# uc4h_slcan_adapter_v101.net
KiCad netlist of a schematic drawn in EAGLE
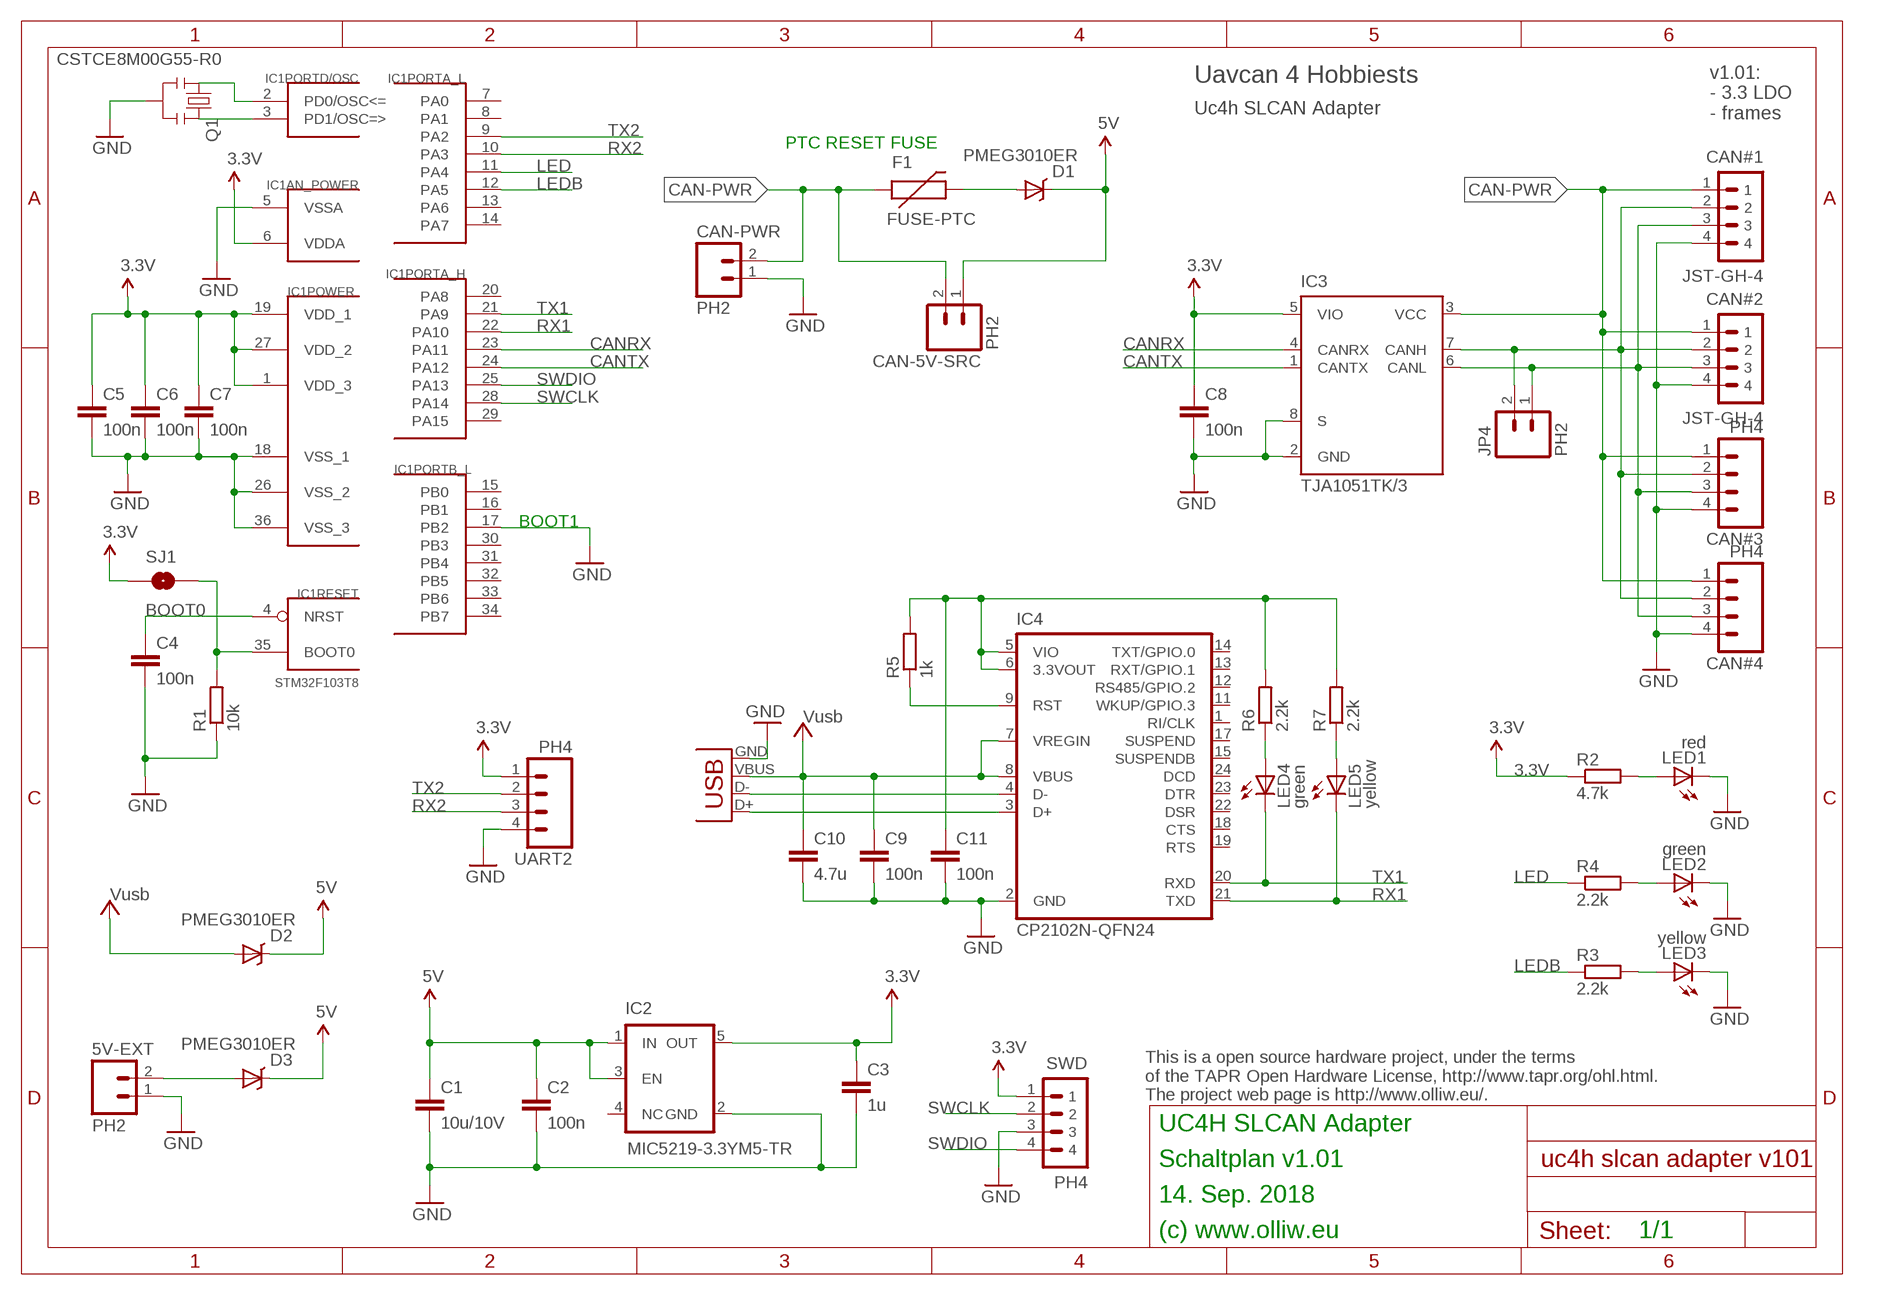
[diagram p0: schematic, sheet 1]

(export (version "E")
  (design (tool "Eeschema 10.0.6"))
  (components
    (comp (ref "5V-EXT")
      (value "PH2")
      (footprint "eagle-import:1X02")
      (libsource (lib "eagle-import") (part "M02PTH"))
    )
    (comp (ref "C1")
      (value "10u/10V")
      (footprint "eagle-import:C1206")
      (libsource (lib "eagle-import") (part "C-EUC1206"))
    )
    (comp (ref "C2")
      (value "100n")
      (footprint "eagle-import:C0603K")
      (libsource (lib "eagle-import") (part "C-EUC0603K"))
    )
    (comp (ref "C3")
      (value "1u")
      (footprint "eagle-import:C0603K")
      (libsource (lib "eagle-import") (part "C-EUC0603K"))
    )
    (comp (ref "C4")
      (value "100n")
      (footprint "eagle-import:C0603K")
      (libsource (lib "eagle-import") (part "C-EUC0603K"))
    )
    (comp (ref "C5")
      (value "100n")
      (footprint "eagle-import:C0603K")
      (libsource (lib "eagle-import") (part "C-EUC0603K"))
    )
    (comp (ref "C6")
      (value "100n")
      (footprint "eagle-import:C0603K")
      (libsource (lib "eagle-import") (part "C-EUC0603K"))
    )
    (comp (ref "C7")
      (value "100n")
      (footprint "eagle-import:C0603K")
      (libsource (lib "eagle-import") (part "C-EUC0603K"))
    )
    (comp (ref "C8")
      (value "100n")
      (footprint "eagle-import:C0603K")
      (libsource (lib "eagle-import") (part "C-EUC0603K"))
    )
    (comp (ref "C9")
      (value "100n")
      (footprint "eagle-import:C0603K")
      (libsource (lib "eagle-import") (part "C-EUC0603K"))
    )
    (comp (ref "C10")
      (value "4.7u")
      (footprint "eagle-import:C0805")
      (libsource (lib "eagle-import") (part "C-EUC0805"))
    )
    (comp (ref "C11")
      (value "100n")
      (footprint "eagle-import:C0603K")
      (libsource (lib "eagle-import") (part "C-EUC0603K"))
    )
    (comp (ref "CAN#1")
      (value "JST-GH-4")
      (footprint "eagle-import:SM04B-GHS-TB")
      (libsource (lib "eagle-import") (part "JST-GH-4"))
    )
    (comp (ref "CAN#2")
      (value "JST-GH-4")
      (footprint "eagle-import:SM04B-GHS-TB")
      (libsource (lib "eagle-import") (part "JST-GH-4"))
    )
    (comp (ref "CAN#3")
      (value "PH4")
      (footprint "eagle-import:1X04")
      (libsource (lib "eagle-import") (part "M04PTH"))
    )
    (comp (ref "CAN#4")
      (value "PH4")
      (footprint "eagle-import:1X04")
      (libsource (lib "eagle-import") (part "M04PTH"))
    )
    (comp (ref "CAN-5V-SRC")
      (value "PH2")
      (footprint "eagle-import:1X02")
      (libsource (lib "eagle-import") (part "M02PTH"))
    )
    (comp (ref "CAN-PWR")
      (value "PH2")
      (footprint "eagle-import:1X02")
      (libsource (lib "eagle-import") (part "M02PTH"))
    )
    (comp (ref "D1")
      (value "PMEG3010ER")
      (footprint "eagle-import:SOD123W-DIODE")
      (libsource (lib "eagle-import") (part "DIODE-SCHOTTKYSOD123-W"))
    )
    (comp (ref "D2")
      (value "PMEG3010ER")
      (footprint "eagle-import:SOD123W-DIODE")
      (libsource (lib "eagle-import") (part "DIODE-SCHOTTKYSOD123-W"))
    )
    (comp (ref "D3")
      (value "PMEG3010ER")
      (footprint "eagle-import:SOD123W-DIODE")
      (libsource (lib "eagle-import") (part "DIODE-SCHOTTKYSOD123-W"))
    )
    (comp (ref "F1")
      (value "FUSE-PTC")
      (footprint "eagle-import:FUSE-1206")
      (libsource (lib "eagle-import") (part "FUSE-PTC"))
    )
    (comp (ref "IC1")
      (value "STM32F103T8")
      (footprint "eagle-import:VFQFPN36")
      (libsource (lib "eagle-import") (part "STM32F10XTXU6"))
    )
    (comp (ref "IC2")
      (value "MIC5219-3.3YM5-TR")
      (footprint "eagle-import:SOT23-5")
      (libsource (lib "eagle-import") (part "V_REG_TPS76433SOT23-5"))
    )
    (comp (ref "IC3")
      (value "TJA1051TK/3")
      (footprint "eagle-import:HVSON8")
      (libsource (lib "eagle-import") (part "TJA1051TK/3"))
    )
    (comp (ref "IC4")
      (value "CP2102N-QFN24")
      (footprint "eagle-import:QFN24-CP2102N")
      (libsource (lib "eagle-import") (part "CP2102N-QFN24"))
    )
    (comp (ref "JP4")
      (value "PH2")
      (footprint "eagle-import:1X02")
      (libsource (lib "eagle-import") (part "M02PTH"))
    )
    (comp (ref "LED1")
      (value "red")
      (footprint "eagle-import:CHIPLED_0603")
      (libsource (lib "eagle-import") (part "LEDCHIPLED_0603"))
    )
    (comp (ref "LED2")
      (value "green")
      (footprint "eagle-import:CHIPLED_0603")
      (libsource (lib "eagle-import") (part "LEDCHIPLED_0603"))
    )
    (comp (ref "LED3")
      (value "yellow")
      (footprint "eagle-import:CHIPLED_0603")
      (libsource (lib "eagle-import") (part "LEDCHIPLED_0603"))
    )
    (comp (ref "LED4")
      (value "green")
      (footprint "eagle-import:CHIPLED_0603")
      (libsource (lib "eagle-import") (part "LEDCHIPLED_0603"))
    )
    (comp (ref "LED5")
      (value "yellow")
      (footprint "eagle-import:CHIPLED_0603")
      (libsource (lib "eagle-import") (part "LEDCHIPLED_0603"))
    )
    (comp (ref "Q1")
      (value "CSTCE8M00G55-R0")
      (footprint "eagle-import:RESONATOR-SMD")
      (libsource (lib "eagle-import") (part "RESONATORSMD"))
    )
    (comp (ref "R1")
      (value "10k")
      (footprint "eagle-import:R0603")
      (libsource (lib "eagle-import") (part "R-EU_R0603"))
    )
    (comp (ref "R2")
      (value "4.7k")
      (footprint "eagle-import:R0603")
      (libsource (lib "eagle-import") (part "R-EU_R0603"))
    )
    (comp (ref "R3")
      (value "2.2k")
      (footprint "eagle-import:R0603")
      (libsource (lib "eagle-import") (part "R-EU_R0603"))
    )
    (comp (ref "R4")
      (value "2.2k")
      (footprint "eagle-import:R0603")
      (libsource (lib "eagle-import") (part "R-EU_R0603"))
    )
    (comp (ref "R5")
      (value "1k")
      (footprint "eagle-import:R0603")
      (libsource (lib "eagle-import") (part "R-EU_R0603"))
    )
    (comp (ref "R6")
      (value "2.2k")
      (footprint "eagle-import:R0603")
      (libsource (lib "eagle-import") (part "R-EU_R0603"))
    )
    (comp (ref "R7")
      (value "2.2k")
      (footprint "eagle-import:R0603")
      (libsource (lib "eagle-import") (part "R-EU_R0603"))
    )
    (comp (ref "SJ1")
      (value "BOOT0")
      (footprint "eagle-import:SJ_2S-NO")
      (libsource (lib "eagle-import") (part "SOLDERJUMPERNO"))
    )
    (comp (ref "SWD")
      (value "PH4")
      (footprint "eagle-import:4X1_1P27_OCT_BILEX")
      (libsource (lib "eagle-import") (part "P4X1_1P27-OCT_BILEX"))
    )
    (comp (ref "UART2")
      (value "PH4")
      (footprint "eagle-import:1X04")
      (libsource (lib "eagle-import") (part "M04PTH"))
    )
    (comp (ref "USB")
      (value "Amphenol 10118192-0001LF")
      (footprint "eagle-import:USB-MICROB")
      (libsource (lib "eagle-import") (part "USB-MICROB"))
    )
  )
  (nets
    (net (code "1") (name "/CANRX") (class "Default")
      (node (ref "IC1") (pin "23") (pinfunction "PA11_23") (pintype "bidirectional"))
      (node (ref "IC3") (pin "4") (pinfunction "CANRX_4") (pintype "output"))
    )
    (net (code "2") (name "/CANTX") (class "Default")
      (node (ref "IC1") (pin "24") (pinfunction "PA12_24") (pintype "bidirectional"))
      (node (ref "IC3") (pin "1") (pinfunction "CANTX_1") (pintype "input"))
    )
    (net (code "3") (name "/LED") (class "Default")
      (node (ref "IC1") (pin "11") (pinfunction "PA4_11") (pintype "bidirectional"))
      (node (ref "R4") (pin "1") (pinfunction "1_1") (pintype "passive"))
    )
    (net (code "4") (name "/LEDB") (class "Default")
      (node (ref "IC1") (pin "12") (pinfunction "PA5_12") (pintype "bidirectional"))
      (node (ref "R3") (pin "1") (pinfunction "1_1") (pintype "passive"))
    )
    (net (code "5") (name "/RX1") (class "Default")
      (node (ref "IC1") (pin "22") (pinfunction "PA10_22") (pintype "bidirectional"))
      (node (ref "IC4") (pin "21") (pinfunction "TXD_21") (pintype "output"))
      (node (ref "LED5") (pin "C") (pinfunction "C_C") (pintype "passive"))
    )
    (net (code "6") (name "/RX2") (class "Default")
      (node (ref "IC1") (pin "10") (pinfunction "PA3_10") (pintype "bidirectional"))
      (node (ref "UART2") (pin "3") (pinfunction "3_3") (pintype "passive"))
    )
    (net (code "7") (name "/SWCLK") (class "Default")
      (node (ref "IC1") (pin "28") (pinfunction "PA14_28") (pintype "bidirectional"))
      (node (ref "SWD") (pin "2") (pinfunction "2_2") (pintype "passive"))
    )
    (net (code "8") (name "/SWDIO") (class "Default")
      (node (ref "IC1") (pin "25") (pinfunction "PA13_25") (pintype "bidirectional"))
      (node (ref "SWD") (pin "4") (pinfunction "4_4") (pintype "passive"))
    )
    (net (code "9") (name "/TX1") (class "Default")
      (node (ref "IC1") (pin "21") (pinfunction "PA9_21") (pintype "bidirectional"))
      (node (ref "IC4") (pin "20") (pinfunction "RXD_20") (pintype "input"))
      (node (ref "LED4") (pin "C") (pinfunction "C_C") (pintype "passive"))
    )
    (net (code "10") (name "/TX2") (class "Default")
      (node (ref "IC1") (pin "9") (pinfunction "PA2_9") (pintype "bidirectional"))
      (node (ref "UART2") (pin "2") (pinfunction "2_2") (pintype "passive"))
    )
    (net (code "11") (name "3.3V") (class "Default")
      (node (ref "C3") (pin "1") (pinfunction "1_1") (pintype "passive"))
      (node (ref "C5") (pin "1") (pinfunction "1_1") (pintype "passive"))
      (node (ref "C6") (pin "1") (pinfunction "1_1") (pintype "passive"))
      (node (ref "C7") (pin "1") (pinfunction "1_1") (pintype "passive"))
      (node (ref "C8") (pin "1") (pinfunction "1_1") (pintype "passive"))
      (node (ref "IC1") (pin "1") (pinfunction "VDD_3_1") (pintype "power_in"))
      (node (ref "IC1") (pin "19") (pinfunction "VDD_1_19") (pintype "power_in"))
      (node (ref "IC1") (pin "27") (pinfunction "VDD_2_27") (pintype "power_in"))
      (node (ref "IC1") (pin "6") (pinfunction "VDDA_6") (pintype "power_in"))
      (node (ref "IC2") (pin "5") (pinfunction "OUT_5") (pintype "output"))
      (node (ref "IC3") (pin "5") (pinfunction "VIO_5") (pintype "power_in"))
      (node (ref "R2") (pin "1") (pinfunction "1_1") (pintype "passive"))
      (node (ref "SJ1") (pin "1") (pinfunction "1_1") (pintype "passive"))
      (node (ref "SWD") (pin "1") (pinfunction "1_1") (pintype "passive"))
      (node (ref "UART2") (pin "1") (pinfunction "1_1") (pintype "passive"))
    )
    (net (code "12") (name "5V") (class "Default")
      (node (ref "C1") (pin "1") (pinfunction "1_1") (pintype "passive"))
      (node (ref "C2") (pin "1") (pinfunction "1_1") (pintype "passive"))
      (node (ref "CAN-5V-SRC") (pin "1") (pinfunction "1_1") (pintype "passive"))
      (node (ref "D1") (pin "C") (pinfunction "C_C") (pintype "passive"))
      (node (ref "D2") (pin "C") (pinfunction "C_C") (pintype "passive"))
      (node (ref "D3") (pin "C") (pinfunction "C_C") (pintype "passive"))
      (node (ref "IC2") (pin "1") (pinfunction "IN_1") (pintype "power_in"))
      (node (ref "IC2") (pin "3") (pinfunction "EN_3") (pintype "input"))
    )
    (net (code "13") (name "CAN-PWR") (class "Default")
      (node (ref "CAN#1") (pin "1") (pinfunction "1_1") (pintype "passive"))
      (node (ref "CAN#2") (pin "1") (pinfunction "1_1") (pintype "passive"))
      (node (ref "CAN#3") (pin "1") (pinfunction "1_1") (pintype "passive"))
      (node (ref "CAN#4") (pin "1") (pinfunction "1_1") (pintype "passive"))
      (node (ref "CAN-5V-SRC") (pin "2") (pinfunction "2_2") (pintype "passive"))
      (node (ref "CAN-PWR") (pin "2") (pinfunction "2_2") (pintype "passive"))
      (node (ref "F1") (pin "3") (pinfunction "1_3") (pintype "bidirectional"))
      (node (ref "IC3") (pin "3") (pinfunction "VCC_3") (pintype "power_in"))
    )
    (net (code "14") (name "GND") (class "Default")
      (node (ref "5V-EXT") (pin "1") (pinfunction "1_1") (pintype "passive"))
      (node (ref "C1") (pin "2") (pinfunction "2_2") (pintype "passive"))
      (node (ref "C10") (pin "2") (pinfunction "2_2") (pintype "passive"))
      (node (ref "C11") (pin "2") (pinfunction "2_2") (pintype "passive"))
      (node (ref "C2") (pin "2") (pinfunction "2_2") (pintype "passive"))
      (node (ref "C3") (pin "2") (pinfunction "2_2") (pintype "passive"))
      (node (ref "C4") (pin "2") (pinfunction "2_2") (pintype "passive"))
      (node (ref "C5") (pin "2") (pinfunction "2_2") (pintype "passive"))
      (node (ref "C6") (pin "2") (pinfunction "2_2") (pintype "passive"))
      (node (ref "C7") (pin "2") (pinfunction "2_2") (pintype "passive"))
      (node (ref "C8") (pin "2") (pinfunction "2_2") (pintype "passive"))
      (node (ref "C9") (pin "2") (pinfunction "2_2") (pintype "passive"))
      (node (ref "CAN#1") (pin "4") (pinfunction "4_4") (pintype "passive"))
      (node (ref "CAN#2") (pin "4") (pinfunction "4_4") (pintype "passive"))
      (node (ref "CAN#3") (pin "4") (pinfunction "4_4") (pintype "passive"))
      (node (ref "CAN#4") (pin "4") (pinfunction "4_4") (pintype "passive"))
      (node (ref "CAN-PWR") (pin "1") (pinfunction "1_1") (pintype "passive"))
      (node (ref "IC1") (pin "17") (pinfunction "PB2_17") (pintype "bidirectional"))
      (node (ref "IC1") (pin "18") (pinfunction "VSS_1_18") (pintype "power_in"))
      (node (ref "IC1") (pin "26") (pinfunction "VSS_2_26") (pintype "power_in"))
      (node (ref "IC1") (pin "36") (pinfunction "VSS_3_36") (pintype "power_in"))
      (node (ref "IC1") (pin "5") (pinfunction "VSSA_5") (pintype "power_in"))
      (node (ref "IC2") (pin "2") (pinfunction "GND_2") (pintype "power_in"))
      (node (ref "IC3") (pin "2") (pinfunction "GND_2") (pintype "power_in"))
      (node (ref "IC3") (pin "8") (pinfunction "S_8") (pintype "input"))
      (node (ref "IC4") (pin "2") (pinfunction "GND_2") (pintype "power_in"))
      (node (ref "LED1") (pin "C") (pinfunction "C_C") (pintype "passive"))
      (node (ref "LED2") (pin "C") (pinfunction "C_C") (pintype "passive"))
      (node (ref "LED3") (pin "C") (pinfunction "C_C") (pintype "passive"))
      (node (ref "Q1") (pin "2") (pinfunction "2_2") (pintype "passive"))
      (node (ref "R1") (pin "1") (pinfunction "1_1") (pintype "passive"))
      (node (ref "SWD") (pin "3") (pinfunction "3_3") (pintype "passive"))
      (node (ref "UART2") (pin "4") (pinfunction "4_4") (pintype "passive"))
      (node (ref "USB") (pin "GND") (pinfunction "GND_GND") (pintype "bidirectional"))
    )
    (net (code "15") (name "Net-(5V-EXT-Pad2)") (class "Default")
      (node (ref "5V-EXT") (pin "2") (pinfunction "2_2") (pintype "passive"))
      (node (ref "D3") (pin "A") (pinfunction "A_A") (pintype "passive"))
    )
    (net (code "16") (name "Net-(F1-2)") (class "Default")
      (node (ref "D1") (pin "A") (pinfunction "A_A") (pintype "passive"))
      (node (ref "F1") (pin "4") (pinfunction "2_4") (pintype "bidirectional"))
    )
    (net (code "17") (name "Net-(IC1E-PD0{slash}OSC<=)") (class "Default")
      (node (ref "IC1") (pin "2") (pinfunction "PD0/OSC<=_2") (pintype "bidirectional"))
      (node (ref "Q1") (pin "1") (pinfunction "1_1") (pintype "passive"))
    )
    (net (code "18") (name "Net-(IC1E-PD1{slash}OSC=>)") (class "Default")
      (node (ref "IC1") (pin "3") (pinfunction "PD1/OSC=>_3") (pintype "bidirectional"))
      (node (ref "Q1") (pin "3") (pinfunction "3_3") (pintype "passive"))
    )
    (net (code "19") (name "Net-(IC1G-BOOT0)") (class "Default")
      (node (ref "IC1") (pin "35") (pinfunction "BOOT0_35") (pintype "input"))
      (node (ref "R1") (pin "2") (pinfunction "2_2") (pintype "passive"))
      (node (ref "SJ1") (pin "2") (pinfunction "2_2") (pintype "passive"))
    )
    (net (code "20") (name "Net-(IC1G-NRST)") (class "Default")
      (node (ref "C4") (pin "1") (pinfunction "1_1") (pintype "passive"))
      (node (ref "IC1") (pin "4") (pinfunction "NRST_4") (pintype "input"))
    )
    (net (code "21") (name "Net-(IC3-CANH)") (class "Default")
      (node (ref "CAN#1") (pin "2") (pinfunction "2_2") (pintype "passive"))
      (node (ref "CAN#2") (pin "2") (pinfunction "2_2") (pintype "passive"))
      (node (ref "CAN#3") (pin "2") (pinfunction "2_2") (pintype "passive"))
      (node (ref "CAN#4") (pin "2") (pinfunction "2_2") (pintype "passive"))
      (node (ref "IC3") (pin "7") (pinfunction "CANH_7") (pintype "bidirectional"))
      (node (ref "JP4") (pin "2") (pinfunction "2_2") (pintype "passive"))
    )
    (net (code "22") (name "Net-(IC3-CANL)") (class "Default")
      (node (ref "CAN#1") (pin "3") (pinfunction "3_3") (pintype "passive"))
      (node (ref "CAN#2") (pin "3") (pinfunction "3_3") (pintype "passive"))
      (node (ref "CAN#3") (pin "3") (pinfunction "3_3") (pintype "passive"))
      (node (ref "CAN#4") (pin "3") (pinfunction "3_3") (pintype "passive"))
      (node (ref "IC3") (pin "6") (pinfunction "CANL_6") (pintype "bidirectional"))
      (node (ref "JP4") (pin "1") (pinfunction "1_1") (pintype "passive"))
    )
    (net (code "23") (name "Net-(IC4-3.3VOUT)") (class "Default")
      (node (ref "C11") (pin "1") (pinfunction "1_1") (pintype "passive"))
      (node (ref "IC4") (pin "5") (pinfunction "VIO_5") (pintype "power_in"))
      (node (ref "IC4") (pin "6") (pinfunction "3.3VOUT_6") (pintype "power_in"))
      (node (ref "R5") (pin "2") (pinfunction "2_2") (pintype "passive"))
      (node (ref "R6") (pin "2") (pinfunction "2_2") (pintype "passive"))
      (node (ref "R7") (pin "2") (pinfunction "2_2") (pintype "passive"))
    )
    (net (code "24") (name "Net-(IC4-D+)") (class "Default")
      (node (ref "IC4") (pin "3") (pinfunction "D+_3") (pintype "bidirectional"))
      (node (ref "USB") (pin "D+") (pinfunction "D+_D+") (pintype "bidirectional"))
    )
    (net (code "25") (name "Net-(IC4-D-)") (class "Default")
      (node (ref "IC4") (pin "4") (pinfunction "D-_4") (pintype "bidirectional"))
      (node (ref "USB") (pin "D-") (pinfunction "D-_D-") (pintype "bidirectional"))
    )
    (net (code "26") (name "Net-(IC4-RST)") (class "Default")
      (node (ref "IC4") (pin "9") (pinfunction "RST_9") (pintype "input"))
      (node (ref "R5") (pin "1") (pinfunction "1_1") (pintype "passive"))
    )
    (net (code "27") (name "Net-(LED1-PadA)") (class "Default")
      (node (ref "LED1") (pin "A") (pinfunction "A_A") (pintype "passive"))
      (node (ref "R2") (pin "2") (pinfunction "2_2") (pintype "passive"))
    )
    (net (code "28") (name "Net-(LED2-PadA)") (class "Default")
      (node (ref "LED2") (pin "A") (pinfunction "A_A") (pintype "passive"))
      (node (ref "R4") (pin "2") (pinfunction "2_2") (pintype "passive"))
    )
    (net (code "29") (name "Net-(LED3-PadA)") (class "Default")
      (node (ref "LED3") (pin "A") (pinfunction "A_A") (pintype "passive"))
      (node (ref "R3") (pin "2") (pinfunction "2_2") (pintype "passive"))
    )
    (net (code "30") (name "Net-(LED4-PadA)") (class "Default")
      (node (ref "LED4") (pin "A") (pinfunction "A_A") (pintype "passive"))
      (node (ref "R6") (pin "1") (pinfunction "1_1") (pintype "passive"))
    )
    (net (code "31") (name "Net-(LED5-PadA)") (class "Default")
      (node (ref "LED5") (pin "A") (pinfunction "A_A") (pintype "passive"))
      (node (ref "R7") (pin "1") (pinfunction "1_1") (pintype "passive"))
    )
    (net (code "32") (name "Vusb") (class "Default")
      (node (ref "C10") (pin "1") (pinfunction "1_1") (pintype "passive"))
      (node (ref "C9") (pin "1") (pinfunction "1_1") (pintype "passive"))
      (node (ref "D2") (pin "A") (pinfunction "A_A") (pintype "passive"))
      (node (ref "IC4") (pin "7") (pinfunction "VREGIN_7") (pintype "power_in"))
      (node (ref "IC4") (pin "8") (pinfunction "VBUS_8") (pintype "input"))
      (node (ref "USB") (pin "VBUS") (pinfunction "VBUS_VBUS") (pintype "bidirectional"))
    )
    (net (code "33") (name "unconnected-(IC1B-PA8-Pad20)") (class "Default")
      (node (ref "IC1") (pin "20") (pinfunction "PA8_20") (pintype "bidirectional"))
    )
    (net (code "34") (name "unconnected-(IC1B-PA15-Pad29)") (class "Default")
      (node (ref "IC1") (pin "29") (pinfunction "PA15_29") (pintype "bidirectional"))
    )
    (net (code "35") (name "unconnected-(IC1C-PA0-Pad7)") (class "Default")
      (node (ref "IC1") (pin "7") (pinfunction "PA0_7") (pintype "bidirectional"))
    )
    (net (code "36") (name "unconnected-(IC1C-PA1-Pad8)") (class "Default")
      (node (ref "IC1") (pin "8") (pinfunction "PA1_8") (pintype "bidirectional"))
    )
    (net (code "37") (name "unconnected-(IC1C-PA6-Pad13)") (class "Default")
      (node (ref "IC1") (pin "13") (pinfunction "PA6_13") (pintype "bidirectional"))
    )
    (net (code "38") (name "unconnected-(IC1C-PA7-Pad14)") (class "Default")
      (node (ref "IC1") (pin "14") (pinfunction "PA7_14") (pintype "bidirectional"))
    )
    (net (code "39") (name "unconnected-(IC1D-PB0-Pad15)") (class "Default")
      (node (ref "IC1") (pin "15") (pinfunction "PB0_15") (pintype "bidirectional"))
    )
    (net (code "40") (name "unconnected-(IC1D-PB1-Pad16)") (class "Default")
      (node (ref "IC1") (pin "16") (pinfunction "PB1_16") (pintype "bidirectional"))
    )
    (net (code "41") (name "unconnected-(IC1D-PB3-Pad30)") (class "Default")
      (node (ref "IC1") (pin "30") (pinfunction "PB3_30") (pintype "bidirectional"))
    )
    (net (code "42") (name "unconnected-(IC1D-PB4-Pad31)") (class "Default")
      (node (ref "IC1") (pin "31") (pinfunction "PB4_31") (pintype "bidirectional"))
    )
    (net (code "43") (name "unconnected-(IC1D-PB5-Pad32)") (class "Default")
      (node (ref "IC1") (pin "32") (pinfunction "PB5_32") (pintype "bidirectional"))
    )
    (net (code "44") (name "unconnected-(IC1D-PB6-Pad33)") (class "Default")
      (node (ref "IC1") (pin "33") (pinfunction "PB6_33") (pintype "bidirectional"))
    )
    (net (code "45") (name "unconnected-(IC1D-PB7-Pad34)") (class "Default")
      (node (ref "IC1") (pin "34") (pinfunction "PB7_34") (pintype "bidirectional"))
    )
    (net (code "46") (name "unconnected-(IC2-NC-Pad4)") (class "Default")
      (node (ref "IC2") (pin "4") (pinfunction "NC_4") (pintype "passive"))
    )
    (net (code "47") (name "unconnected-(IC4-CTS-Pad18)") (class "Default")
      (node (ref "IC4") (pin "18") (pinfunction "CTS_18") (pintype "input"))
    )
    (net (code "48") (name "unconnected-(IC4-DCD-Pad24)") (class "Default")
      (node (ref "IC4") (pin "24") (pinfunction "DCD_24") (pintype "input"))
    )
    (net (code "49") (name "unconnected-(IC4-DSR-Pad22)") (class "Default")
      (node (ref "IC4") (pin "22") (pinfunction "DSR_22") (pintype "input"))
    )
    (net (code "50") (name "unconnected-(IC4-DTR-Pad23)") (class "Default")
      (node (ref "IC4") (pin "23") (pinfunction "DTR_23") (pintype "output"))
    )
    (net (code "51") (name "unconnected-(IC4-RI{slash}CLK-Pad1)") (class "Default")
      (node (ref "IC4") (pin "1") (pinfunction "RI/CLK_1") (pintype "input"))
    )
    (net (code "52") (name "unconnected-(IC4-RS485{slash}GPIO.2-Pad12)") (class "Default")
      (node (ref "IC4") (pin "12") (pinfunction "RS485/GPIO.2_12") (pintype "bidirectional"))
    )
    (net (code "53") (name "unconnected-(IC4-RTS-Pad19)") (class "Default")
      (node (ref "IC4") (pin "19") (pinfunction "RTS_19") (pintype "output"))
    )
    (net (code "54") (name "unconnected-(IC4-RXT{slash}GPIO.1-Pad13)") (class "Default")
      (node (ref "IC4") (pin "13") (pinfunction "RXT/GPIO.1_13") (pintype "bidirectional"))
    )
    (net (code "55") (name "unconnected-(IC4-SUSPEND-Pad17)") (class "Default")
      (node (ref "IC4") (pin "17") (pinfunction "SUSPEND_17") (pintype "output"))
    )
    (net (code "56") (name "unconnected-(IC4-SUSPENDB-Pad15)") (class "Default")
      (node (ref "IC4") (pin "15") (pinfunction "SUSPENDB_15") (pintype "output"))
    )
    (net (code "57") (name "unconnected-(IC4-TXT{slash}GPIO.0-Pad14)") (class "Default")
      (node (ref "IC4") (pin "14") (pinfunction "TXT/GPIO.0_14") (pintype "bidirectional"))
    )
    (net (code "58") (name "unconnected-(IC4-WKUP{slash}GPIO.3-Pad11)") (class "Default")
      (node (ref "IC4") (pin "11") (pinfunction "WKUP/GPIO.3_11") (pintype "bidirectional"))
    )
  )
)
